# Relay_Board.net
KiCad netlist of a schematic drawn in EAGLE
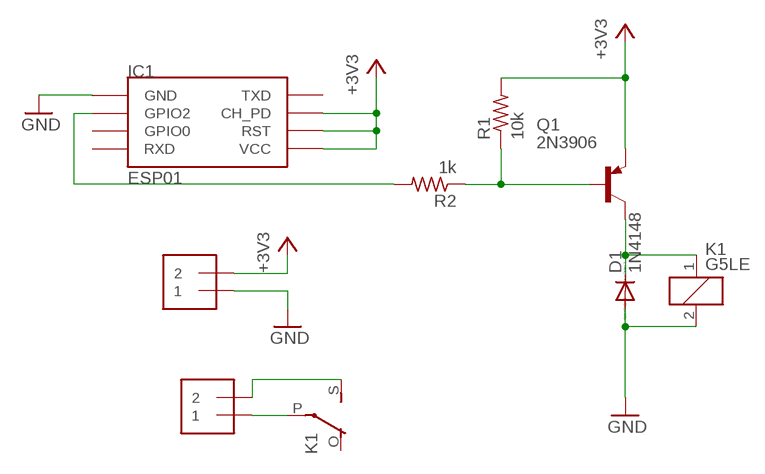
[diagram p0: schematic, sheet 1]

(export (version "E")
  (design (tool "Eeschema 10.0.6"))
  (components
    (comp (ref "D1")
      (value "1N4148")
      (footprint "eagle-import:DO35-7")
      (libsource (lib "eagle-import") (part "1N4148DO35-7"))
    )
    (comp (ref "IC1")
      (value "ESP01")
      (footprint "eagle-import:ESP01")
      (libsource (lib "eagle-import") (part "ESP01"))
    )
    (comp (ref "J1")
      (value "1X2-3.5MM")
      (footprint "eagle-import:1X2-3.5MM")
      (libsource (lib "eagle-import") (part "1X2-3.5MM"))
    )
    (comp (ref "J2")
      (value "1X2-3.5MM")
      (footprint "eagle-import:1X2-3.5MM")
      (libsource (lib "eagle-import") (part "1X2-3.5MM"))
    )
    (comp (ref "K1")
      (value "G5LE")
      (footprint "eagle-import:G5LE")
      (libsource (lib "eagle-import") (part "G5LE"))
    )
    (comp (ref "Q1")
      (value "2N3906")
      (footprint "eagle-import:TO92")
      (libsource (lib "eagle-import") (part "2N3906"))
    )
    (comp (ref "R1")
      (value "10k")
      (footprint "eagle-import:0207_10")
      (libsource (lib "eagle-import") (part "R-US_0207/10"))
    )
    (comp (ref "R2")
      (value "1k")
      (footprint "eagle-import:0207_10")
      (libsource (lib "eagle-import") (part "R-US_0207/10"))
    )
  )
  (nets
    (net (code "1") (name "+3V3") (class "Default")
      (node (ref "IC1") (pin "CH_PD") (pinfunction "CH_PD_CH_PD") (pintype "bidirectional"))
      (node (ref "IC1") (pin "RST") (pinfunction "RST_RST") (pintype "bidirectional"))
      (node (ref "IC1") (pin "VCC") (pinfunction "VCC_VCC") (pintype "bidirectional"))
      (node (ref "J2") (pin "2") (pinfunction "2_2") (pintype "passive"))
      (node (ref "Q1") (pin "3") (pinfunction "E_3") (pintype "passive"))
      (node (ref "R1") (pin "2") (pinfunction "2_2") (pintype "passive"))
    )
    (net (code "2") (name "GND") (class "Default")
      (node (ref "D1") (pin "A") (pinfunction "A_A") (pintype "passive"))
      (node (ref "IC1") (pin "GND") (pinfunction "GND_GND") (pintype "bidirectional"))
      (node (ref "J2") (pin "1") (pinfunction "1_1") (pintype "passive"))
      (node (ref "K1") (pin "2") (pinfunction "2_2") (pintype "passive"))
    )
    (net (code "3") (name "Net-(IC1-PadGPIO2)") (class "Default")
      (node (ref "IC1") (pin "GPIO2") (pinfunction "GPIO2_GPIO2") (pintype "bidirectional"))
      (node (ref "R2") (pin "2") (pinfunction "2_2") (pintype "passive"))
    )
    (net (code "4") (name "Net-(J1-Pad1)") (class "Default")
      (node (ref "J1") (pin "1") (pinfunction "1_1") (pintype "passive"))
      (node (ref "K1") (pin "P") (pinfunction "P_P") (pintype "passive"))
    )
    (net (code "5") (name "Net-(J1-Pad2)") (class "Default")
      (node (ref "J1") (pin "2") (pinfunction "2_2") (pintype "passive"))
      (node (ref "K1") (pin "S") (pinfunction "S_S") (pintype "passive"))
    )
    (net (code "6") (name "Net-(Q1-B)") (class "Default")
      (node (ref "Q1") (pin "2") (pinfunction "B_2") (pintype "passive"))
      (node (ref "R1") (pin "1") (pinfunction "1_1") (pintype "passive"))
      (node (ref "R2") (pin "1") (pinfunction "1_1") (pintype "passive"))
    )
    (net (code "7") (name "Net-(Q1-C)") (class "Default")
      (node (ref "D1") (pin "C") (pinfunction "C_C") (pintype "passive"))
      (node (ref "K1") (pin "1") (pinfunction "1_1") (pintype "passive"))
      (node (ref "Q1") (pin "1") (pinfunction "C_1") (pintype "passive"))
    )
    (net (code "8") (name "unconnected-(IC1-PadGPIO0)") (class "Default")
      (node (ref "IC1") (pin "GPIO0") (pinfunction "GPIO0_GPIO0") (pintype "bidirectional"))
    )
    (net (code "9") (name "unconnected-(IC1-RXD-PadRX)") (class "Default")
      (node (ref "IC1") (pin "RX") (pinfunction "RXD_RX") (pintype "bidirectional"))
    )
    (net (code "10") (name "unconnected-(IC1-TXD-PadTX)") (class "Default")
      (node (ref "IC1") (pin "TX") (pinfunction "TXD_TX") (pintype "bidirectional"))
    )
    (net (code "11") (name "unconnected-(K1-PadO)") (class "Default")
      (node (ref "K1") (pin "O") (pinfunction "O_O") (pintype "passive"))
    )
  )
)
